# Lora_Shield_v1_4.net
KiCad netlist of a schematic drawn in EAGLE
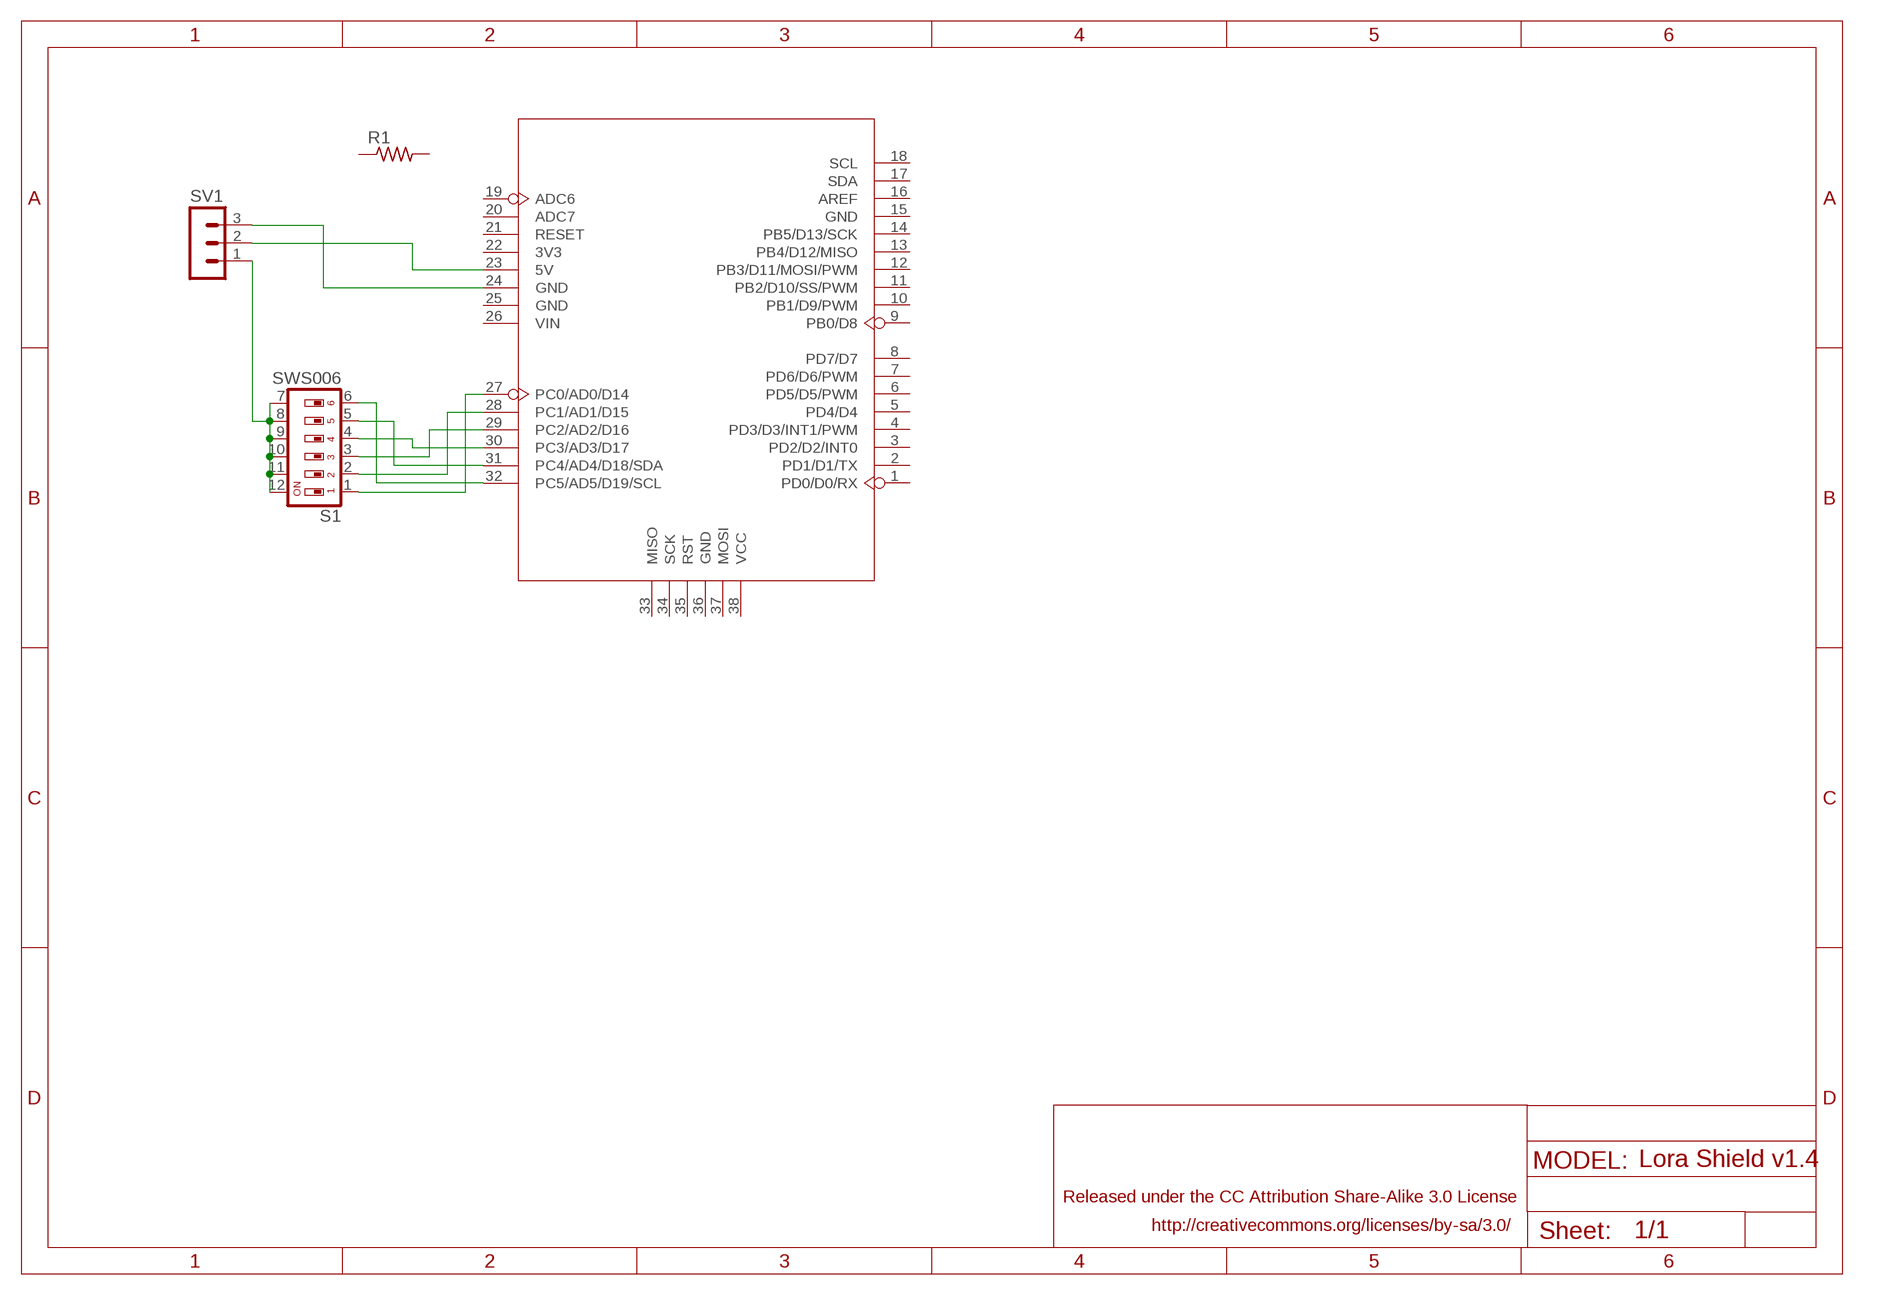
[diagram p0: schematic, sheet 1]

(export (version "E")
  (design (tool "Eeschema 10.0.6"))
  (components
    (comp (ref "R1")
      (value "R-US_R0805")
      (footprint "eagle-import:R0805")
      (libsource (lib "eagle-import") (part "R-US_R0805"))
    )
    (comp (ref "S1")
      (value "SWS006")
      (footprint "eagle-import:SMS-006")
      (libsource (lib "eagle-import") (part "SWS006"))
    )
    (comp (ref "SV1")
      (value "MA03-1")
      (footprint "eagle-import:MA03-1")
      (libsource (lib "eagle-import") (part "MA03-1"))
    )
    (comp (ref "U5")
      (value "MOUDLE_ARDUINO-38P328P_NO_VIA")
      (footprint "eagle-import:MOUDLE_ARDUINO-328P--")
      (libsource (lib "eagle-import") (part "MOUDLE_ARDUINO-38P328P_NO_VIA"))
    )
  )
  (nets
    (net (code "1") (name "Net-(S1-Pad10)") (class "Default")
      (node (ref "S1") (pin "10") (pinfunction "10_10") (pintype "passive"))
      (node (ref "S1") (pin "11") (pinfunction "11_11") (pintype "passive"))
      (node (ref "S1") (pin "12") (pinfunction "12_12") (pintype "passive"))
      (node (ref "S1") (pin "7") (pinfunction "7_7") (pintype "passive"))
      (node (ref "S1") (pin "8") (pinfunction "8_8") (pintype "passive"))
      (node (ref "S1") (pin "9") (pinfunction "9_9") (pintype "passive"))
      (node (ref "SV1") (pin "1") (pinfunction "1_1") (pintype "passive"))
    )
    (net (code "2") (name "Net-(SV1-Pad3)") (class "Default")
      (node (ref "SV1") (pin "3") (pinfunction "3_3") (pintype "passive"))
      (node (ref "U5") (pin "24") (pinfunction "GND_24") (pintype "bidirectional"))
    )
    (net (code "3") (name "Net-(U5-5V)") (class "Default")
      (node (ref "SV1") (pin "2") (pinfunction "2_2") (pintype "passive"))
      (node (ref "U5") (pin "23") (pinfunction "5V_23") (pintype "bidirectional"))
    )
    (net (code "4") (name "Net-(U5-PC0{slash}AD0{slash}D14)") (class "Default")
      (node (ref "S1") (pin "1") (pinfunction "1_1") (pintype "passive"))
      (node (ref "U5") (pin "27") (pinfunction "PC0/AD0/D14_27") (pintype "bidirectional"))
    )
    (net (code "5") (name "Net-(U5-PC1{slash}AD1{slash}D15)") (class "Default")
      (node (ref "S1") (pin "2") (pinfunction "2_2") (pintype "passive"))
      (node (ref "U5") (pin "28") (pinfunction "PC1/AD1/D15_28") (pintype "bidirectional"))
    )
    (net (code "6") (name "Net-(U5-PC2{slash}AD2{slash}D16)") (class "Default")
      (node (ref "S1") (pin "3") (pinfunction "3_3") (pintype "passive"))
      (node (ref "U5") (pin "29") (pinfunction "PC2/AD2/D16_29") (pintype "bidirectional"))
    )
    (net (code "7") (name "Net-(U5-PC3{slash}AD3{slash}D17)") (class "Default")
      (node (ref "S1") (pin "4") (pinfunction "4_4") (pintype "passive"))
      (node (ref "U5") (pin "30") (pinfunction "PC3/AD3/D17_30") (pintype "bidirectional"))
    )
    (net (code "8") (name "Net-(U5-PC4{slash}AD4{slash}D18{slash}SDA)") (class "Default")
      (node (ref "S1") (pin "5") (pinfunction "5_5") (pintype "passive"))
      (node (ref "U5") (pin "31") (pinfunction "PC4/AD4/D18/SDA_31") (pintype "bidirectional"))
    )
    (net (code "9") (name "Net-(U5-PC5{slash}AD5{slash}D19{slash}SCL)") (class "Default")
      (node (ref "S1") (pin "6") (pinfunction "6_6") (pintype "passive"))
      (node (ref "U5") (pin "32") (pinfunction "PC5/AD5/D19/SCL_32") (pintype "bidirectional"))
    )
    (net (code "10") (name "unconnected-(R1-Pad1)") (class "Default")
      (node (ref "R1") (pin "1") (pinfunction "1_1") (pintype "passive"))
    )
    (net (code "11") (name "unconnected-(R1-Pad2)") (class "Default")
      (node (ref "R1") (pin "2") (pinfunction "2_2") (pintype "passive"))
    )
    (net (code "12") (name "unconnected-(U5-3V3-Pad22)") (class "Default")
      (node (ref "U5") (pin "22") (pinfunction "3V3_22") (pintype "bidirectional"))
    )
    (net (code "13") (name "unconnected-(U5-ADC6-Pad19)") (class "Default")
      (node (ref "U5") (pin "19") (pinfunction "ADC6_19") (pintype "bidirectional"))
    )
    (net (code "14") (name "unconnected-(U5-ADC7-Pad20)") (class "Default")
      (node (ref "U5") (pin "20") (pinfunction "ADC7_20") (pintype "bidirectional"))
    )
    (net (code "15") (name "unconnected-(U5-AREF-Pad16)") (class "Default")
      (node (ref "U5") (pin "16") (pinfunction "AREF_16") (pintype "bidirectional"))
    )
    (net (code "16") (name "unconnected-(U5-GND-Pad15)") (class "Default")
      (node (ref "U5") (pin "15") (pinfunction "GND_15") (pintype "bidirectional"))
    )
    (net (code "17") (name "unconnected-(U5-GND-Pad25)") (class "Default")
      (node (ref "U5") (pin "25") (pinfunction "GND_25") (pintype "bidirectional"))
    )
    (net (code "18") (name "unconnected-(U5-GND-Pad36)") (class "Default")
      (node (ref "U5") (pin "36") (pinfunction "GND_36") (pintype "bidirectional"))
    )
    (net (code "19") (name "unconnected-(U5-MISO-Pad33)") (class "Default")
      (node (ref "U5") (pin "33") (pinfunction "MISO_33") (pintype "bidirectional"))
    )
    (net (code "20") (name "unconnected-(U5-MOSI-Pad37)") (class "Default")
      (node (ref "U5") (pin "37") (pinfunction "MOSI_37") (pintype "bidirectional"))
    )
    (net (code "21") (name "unconnected-(U5-PB0{slash}D8-Pad9)") (class "Default")
      (node (ref "U5") (pin "9") (pinfunction "PB0/D8_9") (pintype "bidirectional"))
    )
    (net (code "22") (name "unconnected-(U5-PB1{slash}D9{slash}PWM-Pad10)") (class "Default")
      (node (ref "U5") (pin "10") (pinfunction "PB1/D9/PWM_10") (pintype "bidirectional"))
    )
    (net (code "23") (name "unconnected-(U5-PB2{slash}D10{slash}SS{slash}PWM-Pad11)") (class "Default")
      (node (ref "U5") (pin "11") (pinfunction "PB2/D10/SS/PWM_11") (pintype "bidirectional"))
    )
    (net (code "24") (name "unconnected-(U5-PB3{slash}D11{slash}MOSI{slash}PWM-Pad12)") (class "Default")
      (node (ref "U5") (pin "12") (pinfunction "PB3/D11/MOSI/PWM_12") (pintype "bidirectional"))
    )
    (net (code "25") (name "unconnected-(U5-PB4{slash}D12{slash}MISO-Pad13)") (class "Default")
      (node (ref "U5") (pin "13") (pinfunction "PB4/D12/MISO_13") (pintype "bidirectional"))
    )
    (net (code "26") (name "unconnected-(U5-PB5{slash}D13{slash}SCK-Pad14)") (class "Default")
      (node (ref "U5") (pin "14") (pinfunction "PB5/D13/SCK_14") (pintype "bidirectional"))
    )
    (net (code "27") (name "unconnected-(U5-PD0{slash}D0{slash}RX-Pad1)") (class "Default")
      (node (ref "U5") (pin "1") (pinfunction "PD0/D0/RX_1") (pintype "bidirectional"))
    )
    (net (code "28") (name "unconnected-(U5-PD1{slash}D1{slash}TX-Pad2)") (class "Default")
      (node (ref "U5") (pin "2") (pinfunction "PD1/D1/TX_2") (pintype "bidirectional"))
    )
    (net (code "29") (name "unconnected-(U5-PD2{slash}D2{slash}INT0-Pad3)") (class "Default")
      (node (ref "U5") (pin "3") (pinfunction "PD2/D2/INT0_3") (pintype "bidirectional"))
    )
    (net (code "30") (name "unconnected-(U5-PD3{slash}D3{slash}INT1{slash}PWM-Pad4)") (class "Default")
      (node (ref "U5") (pin "4") (pinfunction "PD3/D3/INT1/PWM_4") (pintype "bidirectional"))
    )
    (net (code "31") (name "unconnected-(U5-PD4{slash}D4-Pad5)") (class "Default")
      (node (ref "U5") (pin "5") (pinfunction "PD4/D4_5") (pintype "bidirectional"))
    )
    (net (code "32") (name "unconnected-(U5-PD5{slash}D5{slash}PWM-Pad6)") (class "Default")
      (node (ref "U5") (pin "6") (pinfunction "PD5/D5/PWM_6") (pintype "bidirectional"))
    )
    (net (code "33") (name "unconnected-(U5-PD6{slash}D6{slash}PWM-Pad7)") (class "Default")
      (node (ref "U5") (pin "7") (pinfunction "PD6/D6/PWM_7") (pintype "bidirectional"))
    )
    (net (code "34") (name "unconnected-(U5-PD7{slash}D7-Pad8)") (class "Default")
      (node (ref "U5") (pin "8") (pinfunction "PD7/D7_8") (pintype "bidirectional"))
    )
    (net (code "35") (name "unconnected-(U5-RESET-Pad21)") (class "Default")
      (node (ref "U5") (pin "21") (pinfunction "RESET_21") (pintype "bidirectional"))
    )
    (net (code "36") (name "unconnected-(U5-RST-Pad35)") (class "Default")
      (node (ref "U5") (pin "35") (pinfunction "RST_35") (pintype "bidirectional"))
    )
    (net (code "37") (name "unconnected-(U5-SCK-Pad34)") (class "Default")
      (node (ref "U5") (pin "34") (pinfunction "SCK_34") (pintype "bidirectional"))
    )
    (net (code "38") (name "unconnected-(U5-SCL-Pad18)") (class "Default")
      (node (ref "U5") (pin "18") (pinfunction "SCL_18") (pintype "bidirectional"))
    )
    (net (code "39") (name "unconnected-(U5-SDA-Pad17)") (class "Default")
      (node (ref "U5") (pin "17") (pinfunction "SDA_17") (pintype "bidirectional"))
    )
    (net (code "40") (name "unconnected-(U5-VCC-Pad38)") (class "Default")
      (node (ref "U5") (pin "38") (pinfunction "VCC_38") (pintype "bidirectional"))
    )
    (net (code "41") (name "unconnected-(U5-VIN-Pad26)") (class "Default")
      (node (ref "U5") (pin "26") (pinfunction "VIN_26") (pintype "bidirectional"))
    )
  )
)
